# 2_Sensor.net
KiCad netlist of a schematic drawn in Altium Designer
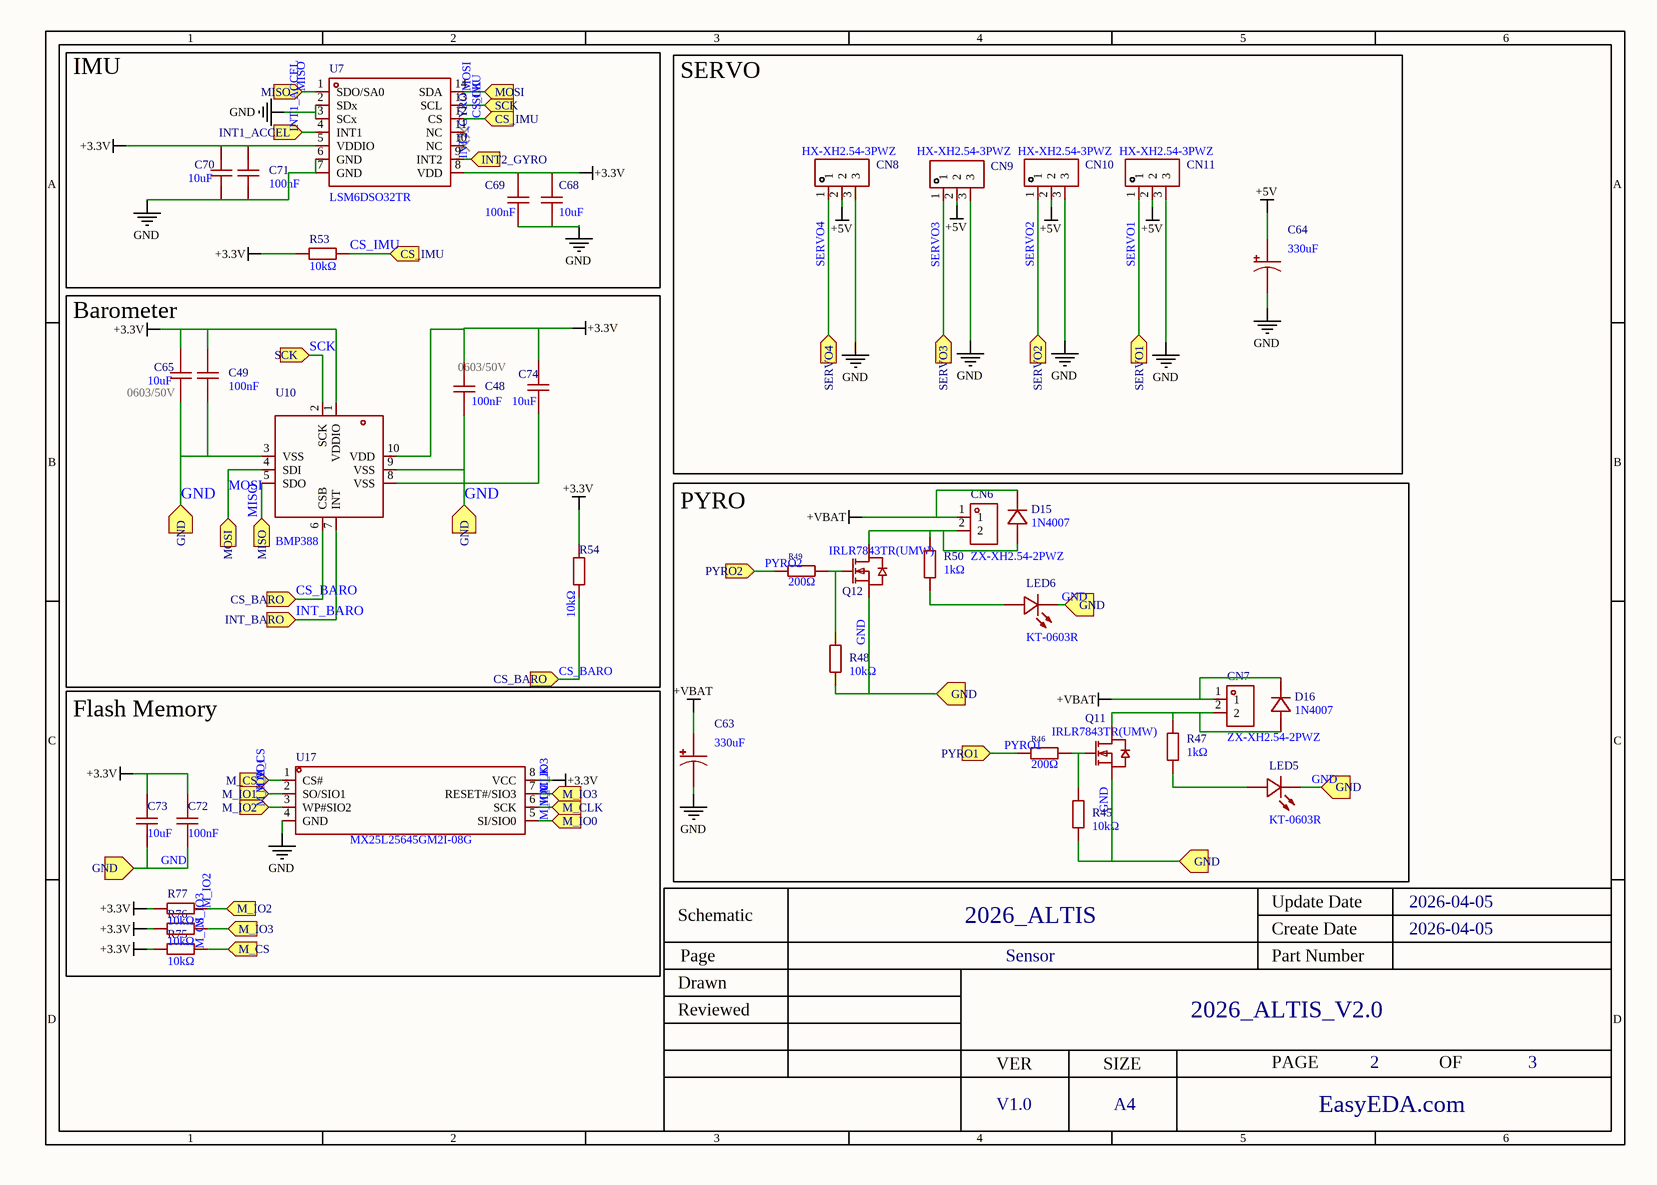
[diagram p0: 2_Sensor.schdoc]

(export (version "E")
  (design (tool "Eeschema 10.0.6"))
  (components
    (comp (ref "C48")
      (value "100nF")
      (footprint "C0603")
      (fields
        (field (name "MANUFACTURER") "YAGEO(国巨)")
        (field (name "MANUFACTURER PART") "CC0603KRX7R9BB104")
        (field (name "TOLERANCE") "±10%")
      )
      (libsource (lib "altium-import") (part "root_1_CC0603KRX7R9BB104_"))
    )
    (comp (ref "C49")
      (value "100nF")
      (footprint "C0603")
      (fields
        (field (name "MANUFACTURER") "YAGEO(国巨)")
        (field (name "MANUFACTURER PART") "CC0603KRX7R9BB104")
        (field (name "TOLERANCE") "±10%")
      )
      (libsource (lib "altium-import") (part "root_1_CC0603KRX7R9BB104_"))
    )
    (comp (ref "C63")
      (value "330uF")
      (footprint "CAP-SMD_BD8.0-L8.3-W8.3-LS9.3-FD-1")
      (fields
        (field (name "MANUFACTURER") "ROQANG(容强)")
        (field (name "MANUFACTURER PART") "RVT1E331M0810")
        (field (name "TOLERANCE") "±20%")
      )
      (libsource (lib "altium-import") (part "root_0_RVT1E331M0810_C335985_"))
    )
    (comp (ref "C64")
      (value "330uF")
      (footprint "CAP-SMD_BD8.0-L8.3-W8.3-LS9.3-FD-1")
      (fields
        (field (name "MANUFACTURER") "ROQANG(容强)")
        (field (name "MANUFACTURER PART") "RVT1E331M0810")
        (field (name "TOLERANCE") "±20%")
      )
      (libsource (lib "altium-import") (part "root_0_RVT1E331M0810_C335985_"))
    )
    (comp (ref "C65")
      (value "10uF")
      (footprint "C0603")
      (fields
        (field (name "MANUFACTURER") "SAMSUNG(三星)")
        (field (name "MANUFACTURER PART") "CL10A106KP8NNNC")
        (field (name "TOLERANCE") "±10%")
      )
      (libsource (lib "altium-import") (part "root_1_CL10A106KP8NNNC_"))
    )
    (comp (ref "C68")
      (value "10uF")
      (footprint "C0603")
      (fields
        (field (name "MANUFACTURER") "SAMSUNG(三星)")
        (field (name "MANUFACTURER PART") "CL10A106KP8NNNC")
        (field (name "TOLERANCE") "±10%")
      )
      (libsource (lib "altium-import") (part "root_1_CL10A106KP8NNNC_"))
    )
    (comp (ref "C69")
      (value "100nF")
      (footprint "C0603")
      (fields
        (field (name "MANUFACTURER") "YAGEO(国巨)")
        (field (name "MANUFACTURER PART") "CC0603KRX7R9BB104")
        (field (name "TOLERANCE") "±10%")
      )
      (libsource (lib "altium-import") (part "root_1_CC0603KRX7R9BB104_"))
    )
    (comp (ref "C70")
      (value "10uF")
      (footprint "C0603")
      (fields
        (field (name "MANUFACTURER") "SAMSUNG(三星)")
        (field (name "MANUFACTURER PART") "CL10A106KP8NNNC")
        (field (name "TOLERANCE") "±10%")
      )
      (libsource (lib "altium-import") (part "root_1_CL10A106KP8NNNC_"))
    )
    (comp (ref "C71")
      (value "100nF")
      (footprint "C0603")
      (fields
        (field (name "MANUFACTURER") "YAGEO(国巨)")
        (field (name "MANUFACTURER PART") "CC0603KRX7R9BB104")
        (field (name "TOLERANCE") "±10%")
      )
      (libsource (lib "altium-import") (part "root_1_CC0603KRX7R9BB104_"))
    )
    (comp (ref "C72")
      (value "100nF")
      (footprint "C0603")
      (fields
        (field (name "MANUFACTURER") "YAGEO(国巨)")
        (field (name "MANUFACTURER PART") "CC0603KRX7R9BB104")
        (field (name "TOLERANCE") "±10%")
      )
      (libsource (lib "altium-import") (part "root_1_CC0603KRX7R9BB104_"))
    )
    (comp (ref "C73")
      (value "10uF")
      (footprint "C0603")
      (fields
        (field (name "MANUFACTURER") "SAMSUNG(三星)")
        (field (name "MANUFACTURER PART") "CL10A106KP8NNNC")
        (field (name "TOLERANCE") "±10%")
      )
      (libsource (lib "altium-import") (part "root_1_CL10A106KP8NNNC_"))
    )
    (comp (ref "C74")
      (value "10uF")
      (footprint "C0603")
      (fields
        (field (name "MANUFACTURER") "SAMSUNG(三星)")
        (field (name "MANUFACTURER PART") "CL10A106KP8NNNC")
        (field (name "TOLERANCE") "±10%")
      )
      (libsource (lib "altium-import") (part "root_1_CL10A106KP8NNNC_"))
    )
    (comp (ref "CN6")
      (value "ZX-XH2.54-2PWZ")
      (footprint "CONN-TH_2P-P2.50_ZX-XH2.54-2PWZ")
      (fields (field (name "MANUFACTURER") "Megastar(兆星)"))
      (libsource (lib "altium-import") (part "root_0_ZX-XH2.54-2PWZ_"))
    )
    (comp (ref "CN7")
      (value "ZX-XH2.54-2PWZ")
      (footprint "CONN-TH_2P-P2.50_ZX-XH2.54-2PWZ")
      (fields (field (name "MANUFACTURER") "Megastar(兆星)"))
      (libsource (lib "altium-import") (part "root_0_ZX-XH2.54-2PWZ_"))
    )
    (comp (ref "CN8")
      (value "HX-XH2.54-3PWZ")
      (footprint "CONN-TH_3P-P2.50_BX-HA2.54-3PWZ")
      (fields (field (name "MANUFACTURER") "hanxia(韩下)"))
      (libsource (lib "altium-import") (part "root_1_HX-XH2.54-3PWZ_"))
    )
    (comp (ref "CN9")
      (value "HX-XH2.54-3PWZ")
      (footprint "CONN-TH_3P-P2.50_BX-HA2.54-3PWZ")
      (fields (field (name "MANUFACTURER") "hanxia(韩下)"))
      (libsource (lib "altium-import") (part "root_1_HX-XH2.54-3PWZ_"))
    )
    (comp (ref "CN10")
      (value "HX-XH2.54-3PWZ")
      (footprint "CONN-TH_3P-P2.50_BX-HA2.54-3PWZ")
      (fields (field (name "MANUFACTURER") "hanxia(韩下)"))
      (libsource (lib "altium-import") (part "root_1_HX-XH2.54-3PWZ_"))
    )
    (comp (ref "CN11")
      (value "HX-XH2.54-3PWZ")
      (footprint "CONN-TH_3P-P2.50_BX-HA2.54-3PWZ")
      (fields (field (name "MANUFACTURER") "hanxia(韩下)"))
      (libsource (lib "altium-import") (part "root_1_HX-XH2.54-3PWZ_"))
    )
    (comp (ref "D15")
      (value "1N4007")
      (footprint "SMA_L4.3-W2.5-LS5.0-RD")
      (fields (field (name "MANUFACTURER") "TWGMC(迪嘉)"))
      (libsource (lib "altium-import") (part "root_3_1N4007_C727081_"))
    )
    (comp (ref "D16")
      (value "1N4007")
      (footprint "SMA_L4.3-W2.5-LS5.0-RD")
      (fields (field (name "MANUFACTURER") "TWGMC(迪嘉)"))
      (libsource (lib "altium-import") (part "root_3_1N4007_C727081_"))
    )
    (comp (ref "LED5")
      (value "KT-0603R")
      (footprint "LED0603-RD")
      (fields (field (name "MANUFACTURER") "KENTO"))
      (libsource (lib "altium-import") (part "root_2_KT-0603R_"))
    )
    (comp (ref "LED6")
      (value "KT-0603R")
      (footprint "LED0603-RD")
      (fields (field (name "MANUFACTURER") "KENTO"))
      (libsource (lib "altium-import") (part "root_2_KT-0603R_"))
    )
    (comp (ref "Q11")
      (value "IRLR7843TR(UMW)")
      (footprint "TO-252-2_L6.5-W6.1-P4.58-LS10.0-BL")
      (fields (field (name "MANUFACTURER") "UMW(友台半导体)"))
      (libsource (lib "altium-import") (part "root_0_IRLR7843TR(UMW)_"))
    )
    (comp (ref "Q12")
      (value "IRLR7843TR(UMW)")
      (footprint "TO-252-2_L6.5-W6.1-P4.58-LS10.0-BL")
      (fields (field (name "MANUFACTURER") "UMW(友台半导体)"))
      (libsource (lib "altium-import") (part "root_0_IRLR7843TR(UMW)_"))
    )
    (comp (ref "R45")
      (value "10kΩ")
      (footprint "R0603")
      (fields
        (field (name "MANUFACTURER") "UNI-ROYAL(厚声)")
        (field (name "MANUFACTURER PART") "0603WAF1002T5E")
        (field (name "TOLERANCE") "±1%")
      )
      (libsource (lib "altium-import") (part "root_1_0603WAF1002T5E_"))
    )
    (comp (ref "R46")
      (value "200Ω")
      (footprint "R0603")
      (fields
        (field (name "MANUFACTURER") "UNI-ROYAL(厚声)")
        (field (name "MANUFACTURER PART") "0603WAF2000T5E")
        (field (name "TOLERANCE") "±1%")
      )
      (libsource (lib "altium-import") (part "root_0_0603WAF2000T5E_"))
    )
    (comp (ref "R47")
      (value "1kΩ")
      (footprint "R0603")
      (fields
        (field (name "MANUFACTURER") "UNI-ROYAL(厚声)")
        (field (name "MANUFACTURER PART") "0603WAF1001T5E")
        (field (name "TOLERANCE") "±1%")
      )
      (libsource (lib "altium-import") (part "root_1_0603WAF1001T5E_"))
    )
    (comp (ref "R48")
      (value "10kΩ")
      (footprint "R0603")
      (fields
        (field (name "MANUFACTURER") "UNI-ROYAL(厚声)")
        (field (name "MANUFACTURER PART") "0603WAF1002T5E")
        (field (name "TOLERANCE") "±1%")
      )
      (libsource (lib "altium-import") (part "root_1_0603WAF1002T5E_"))
    )
    (comp (ref "R49")
      (value "200Ω")
      (footprint "R0603")
      (fields
        (field (name "MANUFACTURER") "UNI-ROYAL(厚声)")
        (field (name "MANUFACTURER PART") "0603WAF2000T5E")
        (field (name "TOLERANCE") "±1%")
      )
      (libsource (lib "altium-import") (part "root_0_0603WAF2000T5E_"))
    )
    (comp (ref "R50")
      (value "1kΩ")
      (footprint "R0603")
      (fields
        (field (name "MANUFACTURER") "UNI-ROYAL(厚声)")
        (field (name "MANUFACTURER PART") "0603WAF1001T5E")
        (field (name "TOLERANCE") "±1%")
      )
      (libsource (lib "altium-import") (part "root_1_0603WAF1001T5E_"))
    )
    (comp (ref "R53")
      (value "10kΩ")
      (footprint "R0603")
      (fields
        (field (name "MANUFACTURER") "UNI-ROYAL(厚声)")
        (field (name "MANUFACTURER PART") "0603WAF1002T5E")
        (field (name "TOLERANCE") "±1%")
      )
      (libsource (lib "altium-import") (part "root_2_0603WAF1002T5E_"))
    )
    (comp (ref "R54")
      (value "10kΩ")
      (footprint "R0603")
      (fields
        (field (name "MANUFACTURER") "UNI-ROYAL(厚声)")
        (field (name "MANUFACTURER PART") "0603WAF1002T5E")
        (field (name "TOLERANCE") "±1%")
      )
      (libsource (lib "altium-import") (part "root_1_0603WAF1002T5E_"))
    )
    (comp (ref "R75")
      (value "10kΩ")
      (footprint "R0603")
      (fields
        (field (name "MANUFACTURER") "UNI-ROYAL(厚声)")
        (field (name "MANUFACTURER PART") "0603WAF1002T5E")
        (field (name "TOLERANCE") "±1%")
      )
      (libsource (lib "altium-import") (part "root_2_0603WAF1002T5E_"))
    )
    (comp (ref "R76")
      (value "10kΩ")
      (footprint "R0603")
      (fields
        (field (name "MANUFACTURER") "UNI-ROYAL(厚声)")
        (field (name "MANUFACTURER PART") "0603WAF1002T5E")
        (field (name "TOLERANCE") "±1%")
      )
      (libsource (lib "altium-import") (part "root_2_0603WAF1002T5E_"))
    )
    (comp (ref "R77")
      (value "10kΩ")
      (footprint "R0603")
      (fields
        (field (name "MANUFACTURER") "UNI-ROYAL(厚声)")
        (field (name "MANUFACTURER PART") "0603WAF1002T5E")
        (field (name "TOLERANCE") "±1%")
      )
      (libsource (lib "altium-import") (part "root_2_0603WAF1002T5E_"))
    )
    (comp (ref "U7")
      (value "LSM6DSO32TR")
      (footprint "LGA-14_L3.0-W2.5-P0.50-TL")
      (fields (field (name "MANUFACTURER") "ST(意法半导体)"))
      (libsource (lib "altium-import") (part "root_0_LSM6DSO32TR_"))
    )
    (comp (ref "U10")
      (value "BMP388")
      (footprint "SENSORM-SMD_BMP388")
      (fields (field (name "MANUFACTURER") "Bosch(博世)"))
      (libsource (lib "altium-import") (part "root_0_BMP388_"))
    )
    (comp (ref "U17")
      (value "MX25L25645GM2I-08G")
      (footprint "SOIC-8_L5.3-W5.3-P1.27-LS8.0-BL")
      (fields (field (name "MANUFACTURER") "MXIC(旺宏电子)"))
      (libsource (lib "altium-import") (part "root_0_MX25L25645GM2I-08G_"))
    )
  )
  (nets
    (net (code "1") (name "+3.3V") (class "Default")
      (node (ref "C48") (pin "2") (pinfunction "2_2") (pintype "passive"))
      (node (ref "C49") (pin "2") (pinfunction "2_2") (pintype "passive"))
      (node (ref "C65") (pin "2") (pinfunction "2_2") (pintype "passive"))
      (node (ref "C68") (pin "2") (pinfunction "2_2") (pintype "passive"))
      (node (ref "C69") (pin "2") (pinfunction "2_2") (pintype "passive"))
      (node (ref "C70") (pin "2") (pinfunction "2_2") (pintype "passive"))
      (node (ref "C71") (pin "2") (pinfunction "2_2") (pintype "passive"))
      (node (ref "C72") (pin "2") (pinfunction "2_2") (pintype "passive"))
      (node (ref "C73") (pin "2") (pinfunction "2_2") (pintype "passive"))
      (node (ref "C74") (pin "2") (pinfunction "2_2") (pintype "passive"))
      (node (ref "R53") (pin "2") (pinfunction "2_2") (pintype "passive"))
      (node (ref "R54") (pin "2") (pinfunction "2_2") (pintype "passive"))
      (node (ref "R75") (pin "2") (pinfunction "2_2") (pintype "passive"))
      (node (ref "R76") (pin "2") (pinfunction "2_2") (pintype "passive"))
      (node (ref "R77") (pin "2") (pinfunction "2_2") (pintype "passive"))
      (node (ref "U10") (pin "1") (pinfunction "VDDIO_1") (pintype "passive"))
      (node (ref "U10") (pin "10") (pinfunction "VDD_10") (pintype "passive"))
      (node (ref "U17") (pin "8") (pinfunction "VCC_8") (pintype "passive"))
      (node (ref "U7") (pin "5") (pinfunction "VDDIO_5") (pintype "passive"))
      (node (ref "U7") (pin "8") (pinfunction "VDD_8") (pintype "passive"))
    )
    (net (code "2") (name "+5V") (class "Default")
      (node (ref "C64") (pin "1") (pinfunction "1_1") (pintype "passive"))
      (node (ref "CN10") (pin "2") (pinfunction "2_2") (pintype "passive"))
      (node (ref "CN11") (pin "2") (pinfunction "2_2") (pintype "passive"))
      (node (ref "CN8") (pin "2") (pinfunction "2_2") (pintype "passive"))
      (node (ref "CN9") (pin "2") (pinfunction "2_2") (pintype "passive"))
    )
    (net (code "3") (name "+VBAT") (class "Default")
      (node (ref "C63") (pin "1") (pinfunction "1_1") (pintype "passive"))
      (node (ref "CN6") (pin "1") (pinfunction "1_1") (pintype "passive"))
      (node (ref "CN7") (pin "1") (pinfunction "1_1") (pintype "passive"))
      (node (ref "D15") (pin "1") (pinfunction "K_1") (pintype "passive"))
      (node (ref "D16") (pin "1") (pinfunction "K_1") (pintype "passive"))
    )
    (net (code "4") (name "/CS_BARO") (class "Default")
      (node (ref "R54") (pin "1") (pinfunction "1_1") (pintype "passive"))
      (node (ref "U10") (pin "6") (pinfunction "CSB_6") (pintype "passive"))
    )
    (net (code "5") (name "/CS_IMU") (class "Default")
      (node (ref "R53") (pin "1") (pinfunction "1_1") (pintype "passive"))
      (node (ref "U7") (pin "12") (pinfunction "CS_12") (pintype "passive"))
    )
    (net (code "6") (name "/INT1_ACCEL") (class "Default")
      (node (ref "U7") (pin "4") (pinfunction "INT1_4") (pintype "passive"))
    )
    (net (code "7") (name "/INT2_GYRO") (class "Default")
      (node (ref "U7") (pin "9") (pinfunction "INT2_9") (pintype "passive"))
    )
    (net (code "8") (name "/INT_BARO") (class "Default")
      (node (ref "U10") (pin "7") (pinfunction "INT_7") (pintype "passive"))
    )
    (net (code "9") (name "/MISO") (class "Default")
      (node (ref "U10") (pin "5") (pinfunction "SDO_5") (pintype "passive"))
      (node (ref "U7") (pin "1") (pinfunction "SDO/SA0_1") (pintype "passive"))
    )
    (net (code "10") (name "/MOSI") (class "Default")
      (node (ref "U10") (pin "4") (pinfunction "SDI_4") (pintype "passive"))
      (node (ref "U7") (pin "14") (pinfunction "SDA_14") (pintype "passive"))
    )
    (net (code "11") (name "/M_CLK") (class "Default")
      (node (ref "U17") (pin "6") (pinfunction "SCK_6") (pintype "passive"))
    )
    (net (code "12") (name "/M_CS") (class "Default")
      (node (ref "R75") (pin "1") (pinfunction "1_1") (pintype "passive"))
      (node (ref "U17") (pin "1") (pinfunction "CS#_1") (pintype "passive"))
    )
    (net (code "13") (name "/M_IO0") (class "Default")
      (node (ref "U17") (pin "5") (pinfunction "SI/SIO0_5") (pintype "passive"))
    )
    (net (code "14") (name "/M_IO1") (class "Default")
      (node (ref "U17") (pin "2") (pinfunction "SO/SIO1_2") (pintype "passive"))
    )
    (net (code "15") (name "/M_IO2") (class "Default")
      (node (ref "R77") (pin "1") (pinfunction "1_1") (pintype "passive"))
      (node (ref "U17") (pin "3") (pinfunction "WP#SIO2_3") (pintype "passive"))
    )
    (net (code "16") (name "/M_IO3") (class "Default")
      (node (ref "R76") (pin "1") (pinfunction "1_1") (pintype "passive"))
      (node (ref "U17") (pin "7") (pinfunction "RESET#/SIO3_7") (pintype "passive"))
    )
    (net (code "17") (name "/PYRO1") (class "Default")
      (node (ref "R46") (pin "1") (pinfunction "1_1") (pintype "passive"))
    )
    (net (code "18") (name "/PYRO2") (class "Default")
      (node (ref "R49") (pin "1") (pinfunction "1_1") (pintype "passive"))
    )
    (net (code "19") (name "/SCK") (class "Default")
      (node (ref "U10") (pin "2") (pinfunction "SCK_2") (pintype "passive"))
      (node (ref "U7") (pin "13") (pinfunction "SCL_13") (pintype "passive"))
    )
    (net (code "20") (name "/SERVO1") (class "Default")
      (node (ref "CN11") (pin "1") (pinfunction "1_1") (pintype "passive"))
    )
    (net (code "21") (name "/SERVO2") (class "Default")
      (node (ref "CN10") (pin "1") (pinfunction "1_1") (pintype "passive"))
    )
    (net (code "22") (name "/SERVO3") (class "Default")
      (node (ref "CN9") (pin "1") (pinfunction "1_1") (pintype "passive"))
    )
    (net (code "23") (name "/SERVO4") (class "Default")
      (node (ref "CN8") (pin "1") (pinfunction "1_1") (pintype "passive"))
    )
    (net (code "24") (name "GND") (class "Default")
      (node (ref "C48") (pin "1") (pinfunction "1_1") (pintype "passive"))
      (node (ref "C49") (pin "1") (pinfunction "1_1") (pintype "passive"))
      (node (ref "C63") (pin "2") (pinfunction "2_2") (pintype "passive"))
      (node (ref "C64") (pin "2") (pinfunction "2_2") (pintype "passive"))
      (node (ref "C65") (pin "1") (pinfunction "1_1") (pintype "passive"))
      (node (ref "C68") (pin "1") (pinfunction "1_1") (pintype "passive"))
      (node (ref "C69") (pin "1") (pinfunction "1_1") (pintype "passive"))
      (node (ref "C70") (pin "1") (pinfunction "1_1") (pintype "passive"))
      (node (ref "C71") (pin "1") (pinfunction "1_1") (pintype "passive"))
      (node (ref "C72") (pin "1") (pinfunction "1_1") (pintype "passive"))
      (node (ref "C73") (pin "1") (pinfunction "1_1") (pintype "passive"))
      (node (ref "C74") (pin "1") (pinfunction "1_1") (pintype "passive"))
      (node (ref "CN10") (pin "3") (pinfunction "3_3") (pintype "passive"))
      (node (ref "CN11") (pin "3") (pinfunction "3_3") (pintype "passive"))
      (node (ref "CN8") (pin "3") (pinfunction "3_3") (pintype "passive"))
      (node (ref "CN9") (pin "3") (pinfunction "3_3") (pintype "passive"))
      (node (ref "LED5") (pin "1") (pinfunction "K_1") (pintype "passive"))
      (node (ref "LED6") (pin "1") (pinfunction "K_1") (pintype "passive"))
      (node (ref "Q11") (pin "3") (pinfunction "S_3") (pintype "passive"))
      (node (ref "Q12") (pin "3") (pinfunction "S_3") (pintype "passive"))
      (node (ref "R45") (pin "1") (pinfunction "1_1") (pintype "passive"))
      (node (ref "R48") (pin "1") (pinfunction "1_1") (pintype "passive"))
      (node (ref "U10") (pin "3") (pinfunction "VSS_3") (pintype "passive"))
      (node (ref "U10") (pin "8") (pinfunction "VSS_8") (pintype "passive"))
      (node (ref "U10") (pin "9") (pinfunction "VSS_9") (pintype "passive"))
      (node (ref "U17") (pin "4") (pinfunction "GND_4") (pintype "passive"))
      (node (ref "U7") (pin "2") (pinfunction "SDx_2") (pintype "passive"))
      (node (ref "U7") (pin "3") (pinfunction "SCx_3") (pintype "passive"))
      (node (ref "U7") (pin "6") (pinfunction "GND_6") (pintype "passive"))
      (node (ref "U7") (pin "7") (pinfunction "GND_7") (pintype "passive"))
    )
    (net (code "25") (name "Net-(D15-A)") (class "Default")
      (node (ref "CN6") (pin "2") (pinfunction "2_2") (pintype "passive"))
      (node (ref "D15") (pin "2") (pinfunction "A_2") (pintype "passive"))
      (node (ref "Q12") (pin "2") (pinfunction "D_2") (pintype "passive"))
      (node (ref "R50") (pin "2") (pinfunction "2_2") (pintype "passive"))
    )
    (net (code "26") (name "Net-(D16-A)") (class "Default")
      (node (ref "CN7") (pin "2") (pinfunction "2_2") (pintype "passive"))
      (node (ref "D16") (pin "2") (pinfunction "A_2") (pintype "passive"))
      (node (ref "Q11") (pin "2") (pinfunction "D_2") (pintype "passive"))
      (node (ref "R47") (pin "2") (pinfunction "2_2") (pintype "passive"))
    )
    (net (code "27") (name "Net-(LED5-A)") (class "Default")
      (node (ref "LED5") (pin "2") (pinfunction "A_2") (pintype "passive"))
      (node (ref "R47") (pin "1") (pinfunction "1_1") (pintype "passive"))
    )
    (net (code "28") (name "Net-(LED6-A)") (class "Default")
      (node (ref "LED6") (pin "2") (pinfunction "A_2") (pintype "passive"))
      (node (ref "R50") (pin "1") (pinfunction "1_1") (pintype "passive"))
    )
    (net (code "29") (name "Net-(Q11-G)") (class "Default")
      (node (ref "Q11") (pin "1") (pinfunction "G_1") (pintype "passive"))
      (node (ref "R45") (pin "2") (pinfunction "2_2") (pintype "passive"))
      (node (ref "R46") (pin "2") (pinfunction "2_2") (pintype "passive"))
    )
    (net (code "30") (name "Net-(Q12-G)") (class "Default")
      (node (ref "Q12") (pin "1") (pinfunction "G_1") (pintype "passive"))
      (node (ref "R48") (pin "2") (pinfunction "2_2") (pintype "passive"))
      (node (ref "R49") (pin "2") (pinfunction "2_2") (pintype "passive"))
    )
    (net (code "31") (name "unconnected-(U7-NC-Pad10)") (class "Default")
      (node (ref "U7") (pin "10") (pinfunction "NC_10") (pintype "passive+no_connect"))
    )
    (net (code "32") (name "unconnected-(U7-NC-Pad11)") (class "Default")
      (node (ref "U7") (pin "11") (pinfunction "NC_11") (pintype "passive+no_connect"))
    )
  )
)
